# Piezoelectric_Energy_Harvester.net
KiCad netlist of a schematic drawn in Altium Designer
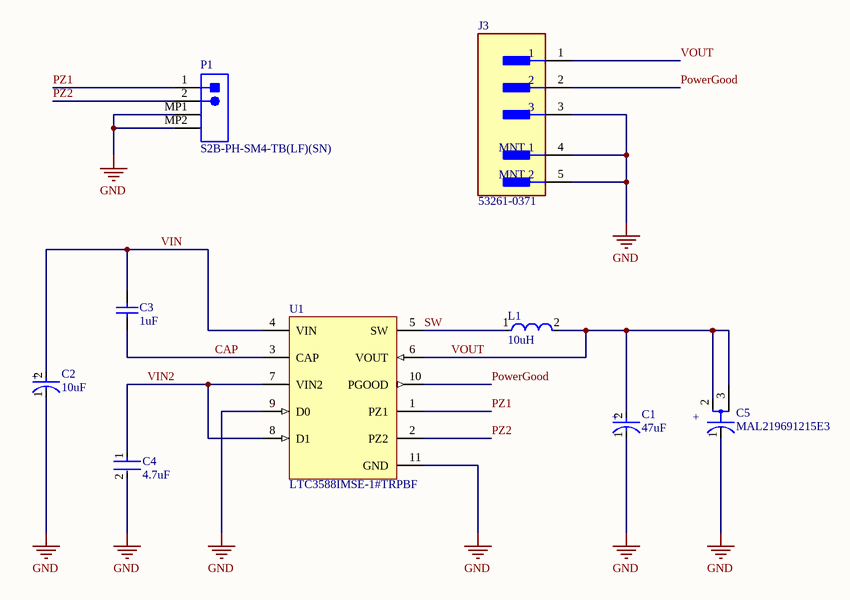
[diagram p0: Piezoelectric Energy Harvester.SchDoc]

(export (version "E")
  (design (tool "Eeschema 10.0.6"))
  (components
    (comp (ref "C1")
      (value "47uF")
      (footprint "FP-T491D476K025AT-MFG")
      (description "CAP TANT 47UF 10% 25V 2917")
      (fields (field (name "VOLTAGE") "25V") (field (name "TOLERANCE") "10%"))
      (libsource (lib "Altium Content Vault") (part "203bc49f2ac43e59fd269a8c329ed05"))
    )
    (comp (ref "C2")
      (value "10uF")
      (footprint "FP-T491D-MFG")
      (description "CAP TANT 10UF 10% 25V 2917")
      (fields (field (name "VOLTAGE") "25V") (field (name "TOLERANCE") "20%"))
      (libsource (lib "Altium Content Vault") (part "cf48714ba7e38822c1575c7ec0b6d1f"))
    )
    (comp (ref "C3")
      (value "1uF")
      (footprint "CAPC3216X110X50LL20T25")
      (description "Chip Capacitor, 1 uF, +/- 10%, 50 V, -55 to 125 degC, 1206 (3216 Metric), RoHS, Tape and Reel")
      (fields (field (name "MANUFACTURER") "Kemet") (field (name "TOLERANCE") "10%"))
      (libsource (lib "Altium Content Vault") (part "CAP-NP-2"))
    )
    (comp (ref "C4")
      (value "4.7uF")
      (footprint "FP-GRM31C-0_2-e0_3_0_8-IPC_B")
      (description "Chip Multilayer Ceramic Capacitors for General Purpose, 1206, 4.7uF, X7R, 15%, 10%, 50V")
      (fields (field (name "VOLTAGE") "50V") (field (name "TOLERANCE") "10%"))
      (libsource (lib "Altium Content Vault") (part "02cd4be3c70576c341d710602a673aa"))
    )
    (comp (ref "C5")
      (value "MAL219691215E3")
      (footprint "FP-MAL219691215E3-MFG")
      (description "CAP 15F -20% +80% 7V T/H")
      (fields (field (name "TOLERANCE") "80%") (field (name "VOLTAGE") "7V"))
      (libsource (lib "Altium Content Vault") (part "5ac0aa9aef3c59413713b00ec7954cf"))
    )
    (comp (ref "J3")
      (value "53261-0371")
      (footprint "FP-53261-0371-MFG")
      (description "CONN HEADER SMD R/A 3POS 1.25MM")
      (fields
        (field (name "MANUFACTURER") "Molex")
        (field (name "OCTOPART") "https://octopart.com/53261-0371-molex-655314")
      )
      (libsource (lib "Altium Content Vault") (part "13850a6865a90496d8e6d51657cef87"))
    )
    (comp (ref "L1")
      (value "10uH")
      (footprint "FP-NR6045-MFG")
      (description "Shielded Wirewound Inductor 10uH 20% 2.5A 61.1mΩ SMD")
      (fields (field (name "TOLERANCE") "20%"))
      (libsource (lib "Altium Content Vault") (part "725321dda6339637d4d059423bc1c3c"))
    )
    (comp (ref "P1")
      (value "S2B-PH-SM4-TB(LF)(SN)")
      (footprint "JST- S2B-PH-SM4-TB(LF)(SN)-2_V")
      (description "Male Header, Pitch 2 mm, 1 x 2 Position, Height 5.5 mm, -25 to 85 degC, RoHS, Tape and Reel")
      (libsource (lib "Altium Content Vault") (part "CN-1P-2M-R2"))
    )
    (comp (ref "U1")
      (value "LTC3588IMSE-1#TRPBF")
      (footprint "LT-MSE-10-EDP_L")
      (fields (field (name "MANUFACTURER") "Linear Technology"))
      (libsource (lib "Altium Content Vault") (part "LT-LTC3588-10"))
    )
  )
  (nets
    (net (code "1") (name "/CAP") (class "Default")
      (node (ref "C3") (pin "1") (pinfunction "1_1") (pintype "passive"))
      (node (ref "U1") (pin "3") (pinfunction "CAP_3") (pintype "passive"))
    )
    (net (code "2") (name "/PZ1") (class "Default")
      (node (ref "P1") (pin "1") (pinfunction "1_1") (pintype "passive"))
      (node (ref "U1") (pin "1") (pinfunction "PZ1_1") (pintype "power_in"))
    )
    (net (code "3") (name "/PZ2") (class "Default")
      (node (ref "P1") (pin "2") (pinfunction "2_2") (pintype "passive"))
      (node (ref "U1") (pin "2") (pinfunction "PZ2_2") (pintype "power_in"))
    )
    (net (code "4") (name "/PowerGood") (class "Default")
      (node (ref "J3") (pin "2") (pinfunction "2_2") (pintype "passive"))
      (node (ref "U1") (pin "10") (pinfunction "PGOOD_10") (pintype "output"))
    )
    (net (code "5") (name "/SW") (class "Default")
      (node (ref "L1") (pin "1") (pinfunction "1_1") (pintype "passive"))
      (node (ref "U1") (pin "5") (pinfunction "SW_5") (pintype "power_in"))
    )
    (net (code "6") (name "/VIN") (class "Default")
      (node (ref "C2") (pin "2") (pinfunction "A_2") (pintype "passive"))
      (node (ref "C3") (pin "2") (pinfunction "2_2") (pintype "passive"))
      (node (ref "U1") (pin "4") (pinfunction "VIN_4") (pintype "power_in"))
    )
    (net (code "7") (name "/VIN2") (class "Default")
      (node (ref "C4") (pin "1") (pinfunction "1_1") (pintype "passive"))
      (node (ref "U1") (pin "7") (pinfunction "VIN2_7") (pintype "power_in"))
      (node (ref "U1") (pin "8") (pinfunction "D1_8") (pintype "input"))
    )
    (net (code "8") (name "/VOUT") (class "Default")
      (node (ref "C1") (pin "2") (pinfunction "A_2") (pintype "passive"))
      (node (ref "C5") (pin "2") (pinfunction "A_2") (pintype "passive"))
      (node (ref "C5") (pin "3") (pinfunction "A_3") (pintype "passive"))
      (node (ref "J3") (pin "1") (pinfunction "1_1") (pintype "passive"))
      (node (ref "L1") (pin "2") (pinfunction "2_2") (pintype "passive"))
      (node (ref "U1") (pin "6") (pinfunction "VOUT_6") (pintype "input"))
    )
    (net (code "9") (name "GND") (class "Default")
      (node (ref "C1") (pin "1") (pinfunction "C_1") (pintype "passive"))
      (node (ref "C2") (pin "1") (pinfunction "C_1") (pintype "passive"))
      (node (ref "C4") (pin "2") (pinfunction "2_2") (pintype "passive"))
      (node (ref "C5") (pin "1") (pinfunction "C_1") (pintype "passive"))
      (node (ref "J3") (pin "3") (pinfunction "3_3") (pintype "passive"))
      (node (ref "J3") (pin "4") (pinfunction "MNT_1_4") (pintype "passive"))
      (node (ref "J3") (pin "5") (pinfunction "MNT_2_5") (pintype "passive"))
      (node (ref "P1") (pin "MP1") (pinfunction "MP1_MP1") (pintype "passive"))
      (node (ref "P1") (pin "MP2") (pinfunction "MP2_MP2") (pintype "passive"))
      (node (ref "U1") (pin "11") (pinfunction "GND_11") (pintype "power_in"))
      (node (ref "U1") (pin "9") (pinfunction "D0_9") (pintype "input"))
    )
  )
)
